# ExpBoard.net
KiCad netlist of a schematic drawn in EAGLE
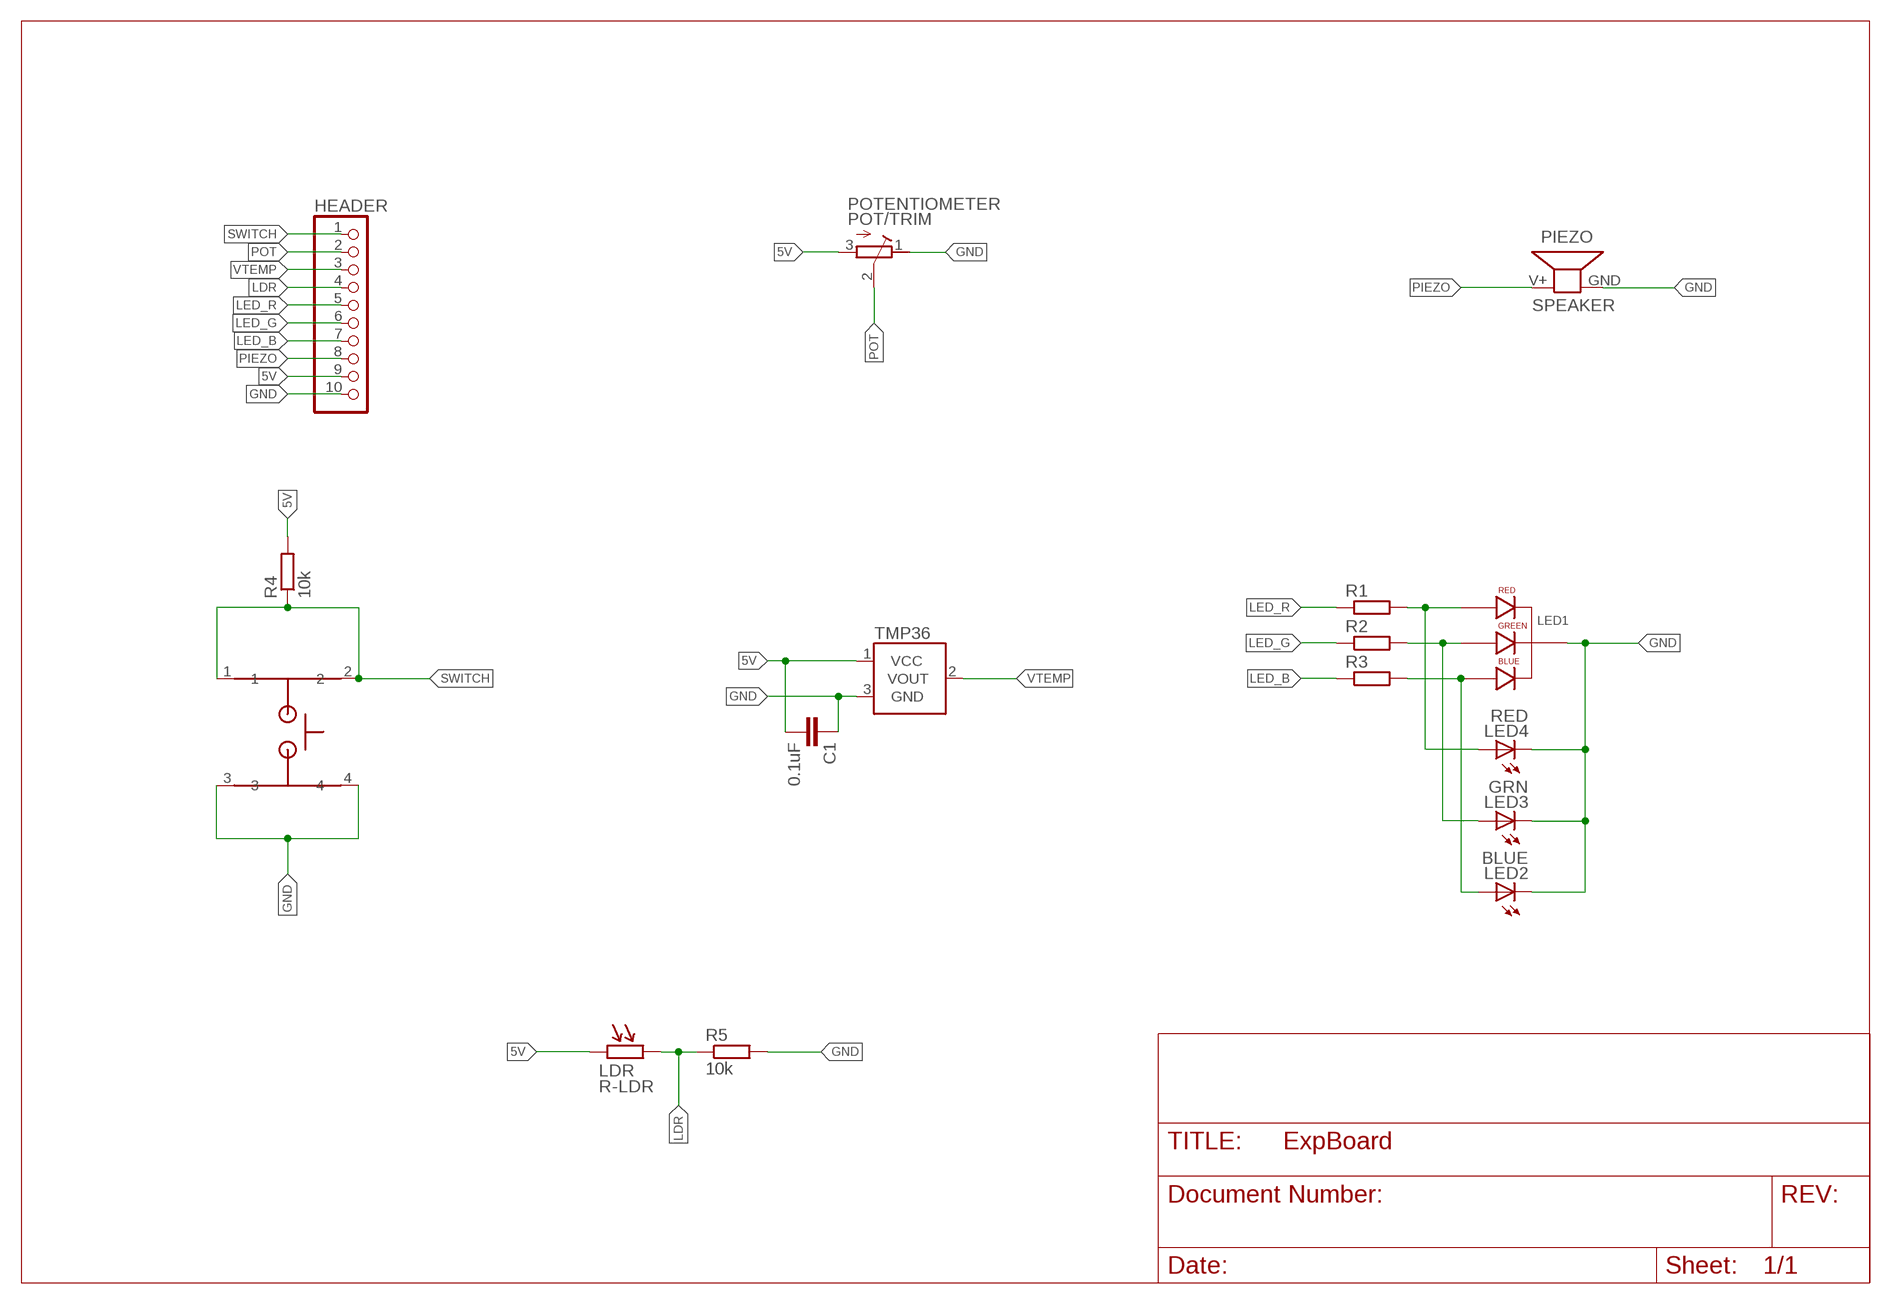
[diagram p0: schematic, sheet 1]

(export (version "E")
  (design (tool "Eeschema 10.0.6"))
  (components
    (comp (ref "C1")
      (value "0.1uF")
      (footprint "eagle-import:C050-035X075")
      (libsource (lib "eagle-import") (part "C-EU050-035X075"))
    )
    (comp (ref "HEADER")
      (value "PINHD-1X10")
      (footprint "eagle-import:1X10")
      (libsource (lib "eagle-import") (part "PINHD-1X10"))
    )
    (comp (ref "LDR")
      (value "R-LDR")
      (footprint "eagle-import:LDR_RE04698")
      (libsource (lib "eagle-import") (part "R-LDR"))
    )
    (comp (ref "LED1")
      (value "LED")
      (footprint "eagle-import:LED-RGB-TH")
      (libsource (lib "eagle-import") (part "mjholmes_LED"))
    )
    (comp (ref "LED2")
      (value "BLUE")
      (footprint "eagle-import:LED5MM")
      (libsource (lib "eagle-import") (part "LED5MM"))
    )
    (comp (ref "LED3")
      (value "GRN")
      (footprint "eagle-import:LED5MM")
      (libsource (lib "eagle-import") (part "LED5MM"))
    )
    (comp (ref "LED4")
      (value "RED")
      (footprint "eagle-import:LED5MM")
      (libsource (lib "eagle-import") (part "LED5MM"))
    )
    (comp (ref "PIEZO")
      (value "SPEAKER")
      (footprint "eagle-import:PIEZO_LS03781")
      (libsource (lib "eagle-import") (part "SPEAKER"))
    )
    (comp (ref "POTENTIOMETER")
      (value "POT/TRIM")
      (footprint "eagle-import:TRIM_RE06540")
      (libsource (lib "eagle-import") (part "POT/TRIM"))
    )
    (comp (ref "R1")
      (value "R-EU_0204/7")
      (footprint "eagle-import:0204_7")
      (libsource (lib "eagle-import") (part "R-EU_0204/7"))
    )
    (comp (ref "R2")
      (value "R-EU_0204/7")
      (footprint "eagle-import:0204_7")
      (libsource (lib "eagle-import") (part "R-EU_0204/7"))
    )
    (comp (ref "R3")
      (value "R-EU_0204/7")
      (footprint "eagle-import:0204_7")
      (libsource (lib "eagle-import") (part "R-EU_0204/7"))
    )
    (comp (ref "R4")
      (value "10k")
      (footprint "eagle-import:0204_7")
      (libsource (lib "eagle-import") (part "R-EU_0204/7"))
    )
    (comp (ref "R5")
      (value "10k")
      (footprint "eagle-import:0204_7")
      (libsource (lib "eagle-import") (part "R-EU_0204/7"))
    )
    (comp (ref "SWITCH")
      (value "SWITCH")
      (footprint "eagle-import:SKHHAMA010")
      (libsource (lib "eagle-import") (part "SWITCH"))
    )
    (comp (ref "TMP36")
      (value "TMP36GT9")
      (footprint "eagle-import:TO-92")
      (libsource (lib "eagle-import") (part "TMP36GT9"))
    )
  )
  (nets
    (net (code "1") (name "5V") (class "Default")
      (node (ref "C1") (pin "2") (pinfunction "2_2") (pintype "passive"))
      (node (ref "HEADER") (pin "9") (pinfunction "9_9") (pintype "passive"))
      (node (ref "LDR") (pin "1") (pinfunction "1_1") (pintype "passive"))
      (node (ref "POTENTIOMETER") (pin "3") (pinfunction "E_3") (pintype "passive"))
      (node (ref "R4") (pin "2") (pinfunction "2_2") (pintype "passive"))
      (node (ref "TMP36") (pin "1") (pinfunction "VCC_1") (pintype "bidirectional"))
    )
    (net (code "2") (name "GND") (class "Default")
      (node (ref "C1") (pin "1") (pinfunction "1_1") (pintype "passive"))
      (node (ref "HEADER") (pin "10") (pinfunction "10_10") (pintype "passive"))
      (node (ref "LED1") (pin "3") (pinfunction "CATHODE_3") (pintype "bidirectional"))
      (node (ref "LED2") (pin "K") (pinfunction "C_K") (pintype "passive"))
      (node (ref "LED3") (pin "K") (pinfunction "C_K") (pintype "passive"))
      (node (ref "LED4") (pin "K") (pinfunction "C_K") (pintype "passive"))
      (node (ref "PIEZO") (pin "GND") (pinfunction "2_GND") (pintype "passive"))
      (node (ref "POTENTIOMETER") (pin "1") (pinfunction "A_1") (pintype "passive"))
      (node (ref "R5") (pin "2") (pinfunction "2_2") (pintype "passive"))
      (node (ref "SWITCH") (pin "3") (pinfunction "3_3") (pintype "bidirectional"))
      (node (ref "SWITCH") (pin "4") (pinfunction "4_4") (pintype "bidirectional"))
      (node (ref "TMP36") (pin "3") (pinfunction "GND_3") (pintype "bidirectional"))
    )
    (net (code "3") (name "LDR") (class "Default")
      (node (ref "HEADER") (pin "4") (pinfunction "4_4") (pintype "passive"))
      (node (ref "LDR") (pin "2") (pinfunction "2_2") (pintype "passive"))
      (node (ref "R5") (pin "1") (pinfunction "1_1") (pintype "passive"))
    )
    (net (code "4") (name "LED_B") (class "Default")
      (node (ref "HEADER") (pin "7") (pinfunction "7_7") (pintype "passive"))
      (node (ref "R3") (pin "1") (pinfunction "1_1") (pintype "passive"))
    )
    (net (code "5") (name "LED_G") (class "Default")
      (node (ref "HEADER") (pin "6") (pinfunction "6_6") (pintype "passive"))
      (node (ref "R2") (pin "1") (pinfunction "1_1") (pintype "passive"))
    )
    (net (code "6") (name "LED_R") (class "Default")
      (node (ref "HEADER") (pin "5") (pinfunction "5_5") (pintype "passive"))
      (node (ref "R1") (pin "1") (pinfunction "1_1") (pintype "passive"))
    )
    (net (code "7") (name "Net-(LED1-BLUE_ANODE)") (class "Default")
      (node (ref "LED1") (pin "1") (pinfunction "BLUE_ANODE_1") (pintype "bidirectional"))
      (node (ref "LED2") (pin "A") (pinfunction "A_A") (pintype "passive"))
      (node (ref "R3") (pin "2") (pinfunction "2_2") (pintype "passive"))
    )
    (net (code "8") (name "Net-(LED1-GREEN_ANODE)") (class "Default")
      (node (ref "LED1") (pin "2") (pinfunction "GREEN_ANODE_2") (pintype "bidirectional"))
      (node (ref "LED3") (pin "A") (pinfunction "A_A") (pintype "passive"))
      (node (ref "R2") (pin "2") (pinfunction "2_2") (pintype "passive"))
    )
    (net (code "9") (name "Net-(LED1-RED_ANODE)") (class "Default")
      (node (ref "LED1") (pin "4") (pinfunction "RED_ANODE_4") (pintype "bidirectional"))
      (node (ref "LED4") (pin "A") (pinfunction "A_A") (pintype "passive"))
      (node (ref "R1") (pin "2") (pinfunction "2_2") (pintype "passive"))
    )
    (net (code "10") (name "PIEZO") (class "Default")
      (node (ref "HEADER") (pin "8") (pinfunction "8_8") (pintype "passive"))
      (node (ref "PIEZO") (pin "V+") (pinfunction "1_V+") (pintype "passive"))
    )
    (net (code "11") (name "POT") (class "Default")
      (node (ref "HEADER") (pin "2") (pinfunction "2_2") (pintype "passive"))
      (node (ref "POTENTIOMETER") (pin "2") (pinfunction "S_2") (pintype "passive"))
    )
    (net (code "12") (name "SWITCH") (class "Default")
      (node (ref "HEADER") (pin "1") (pinfunction "1_1") (pintype "passive"))
      (node (ref "R4") (pin "1") (pinfunction "1_1") (pintype "passive"))
      (node (ref "SWITCH") (pin "1") (pinfunction "1_1") (pintype "bidirectional"))
      (node (ref "SWITCH") (pin "2") (pinfunction "2_2") (pintype "bidirectional"))
    )
    (net (code "13") (name "VTEMP") (class "Default")
      (node (ref "HEADER") (pin "3") (pinfunction "3_3") (pintype "passive"))
      (node (ref "TMP36") (pin "2") (pinfunction "VOUT_2") (pintype "bidirectional"))
    )
  )
)
